# Untitled.net
KiCad netlist of a schematic drawn in EAGLE
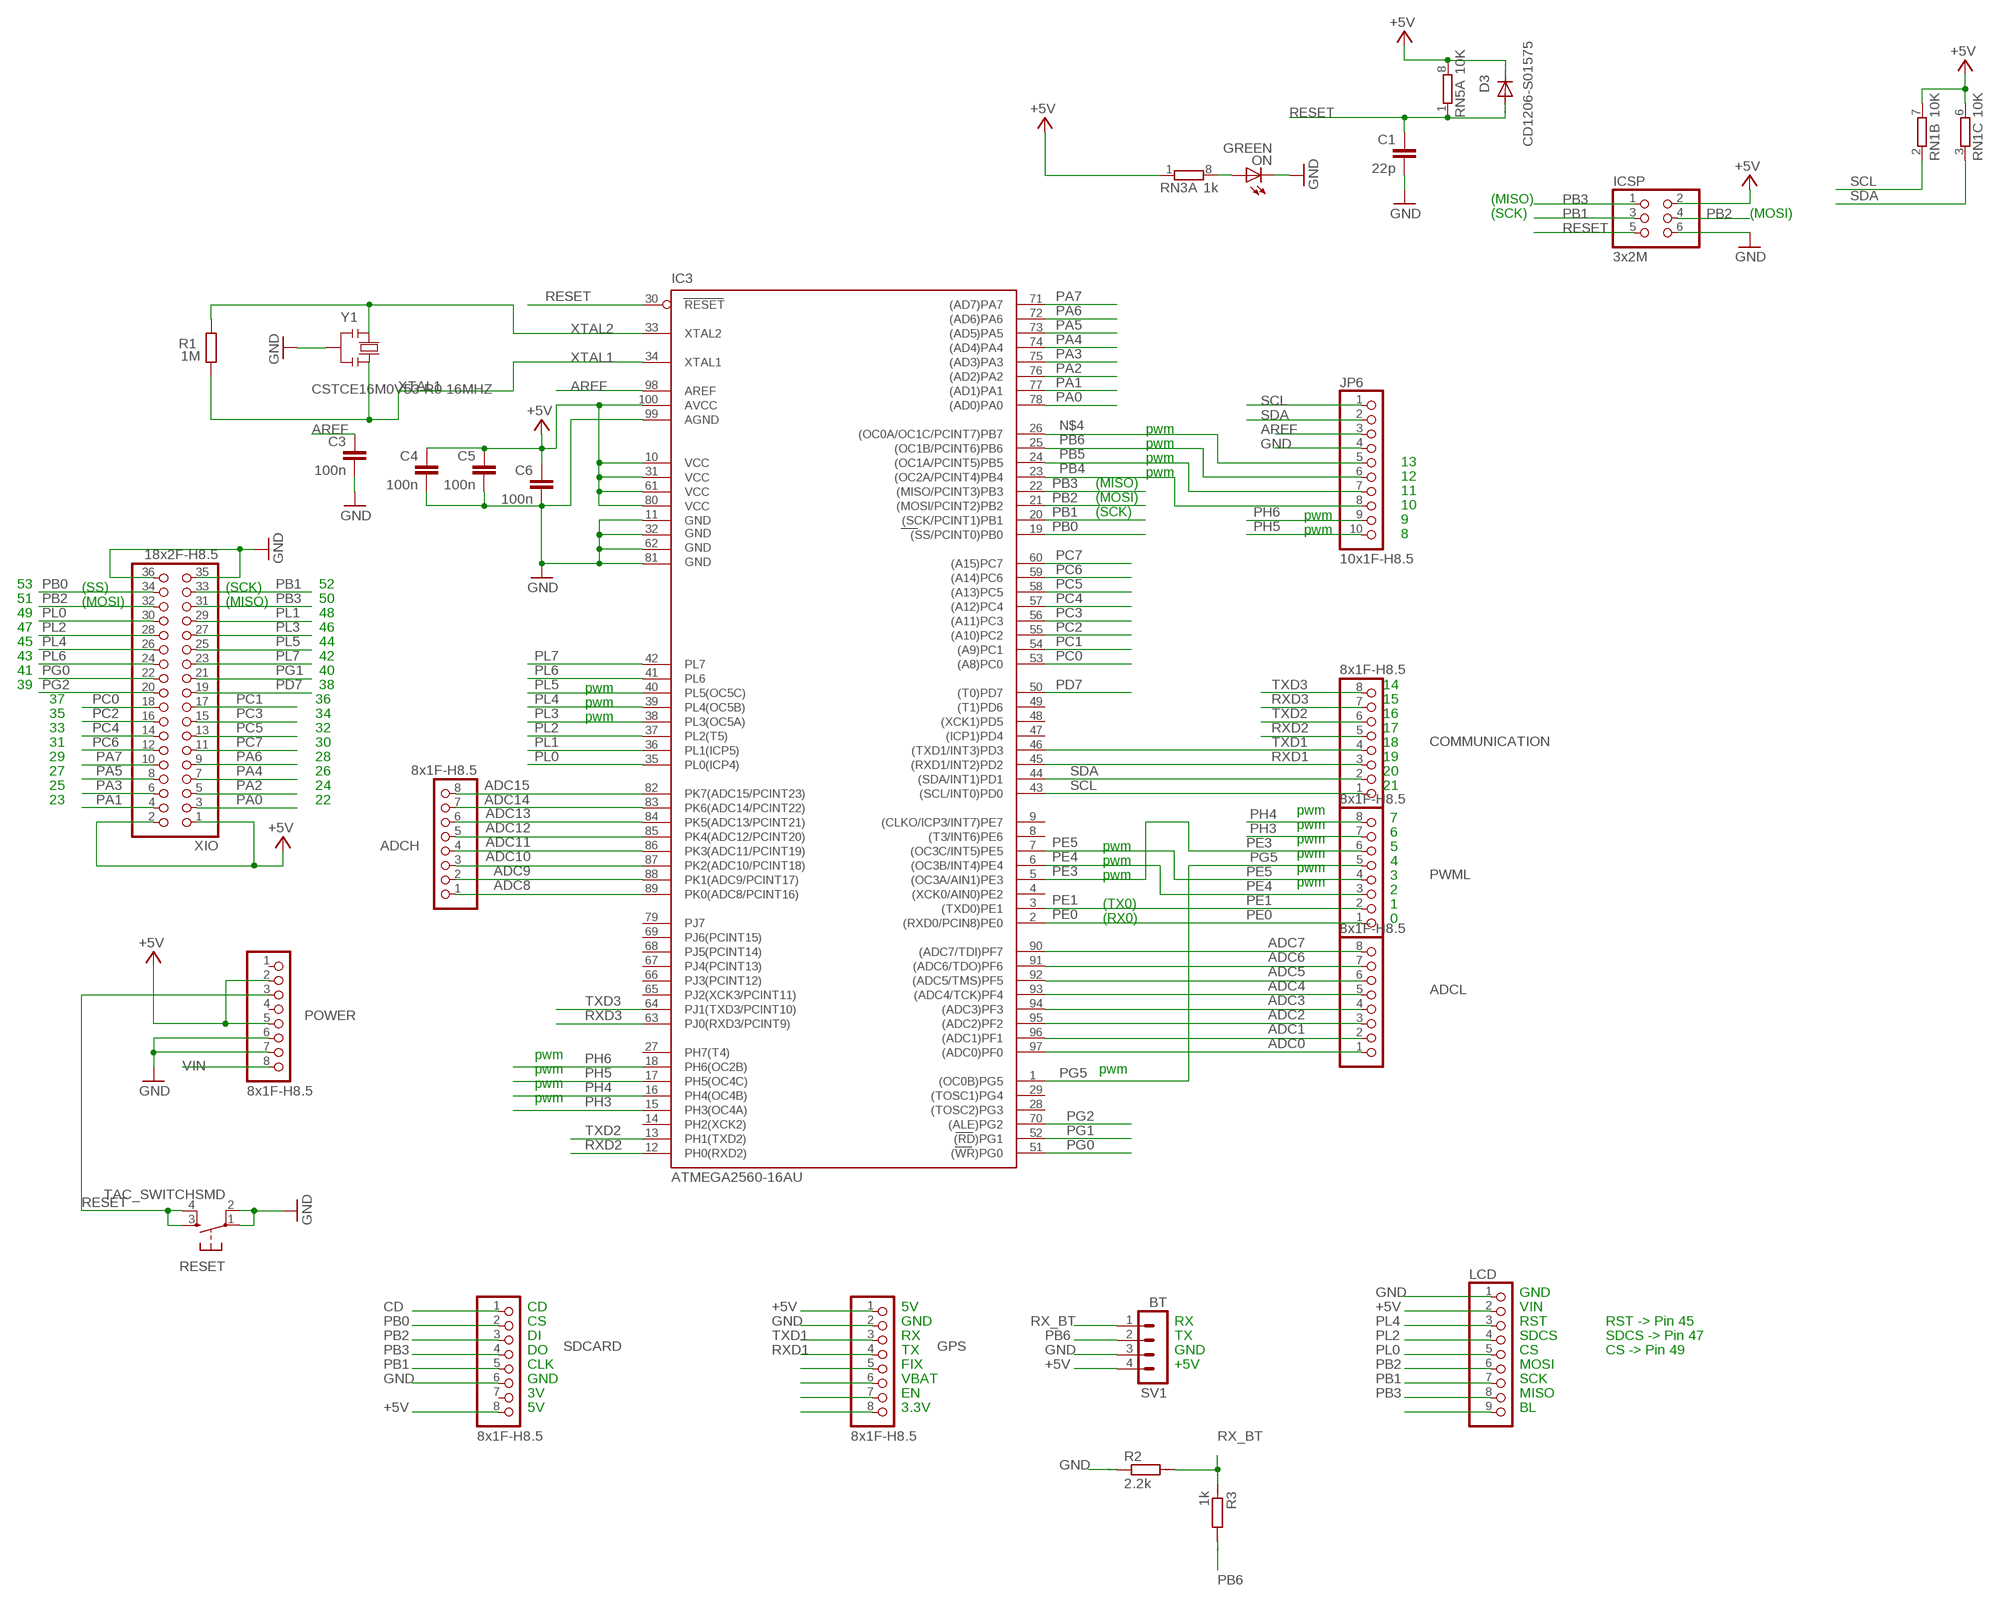
[diagram p0: schematic, sheet 1]

(export (version "E")
  (design (tool "Eeschema 10.0.6"))
  (components
    (comp (ref "ADCH")
      (value "8x1F-H8.5")
      (footprint "eagle-import:1X08")
      (libsource (lib "eagle-import") (part "PINHD-1X8"))
    )
    (comp (ref "ADCL")
      (value "8x1F-H8.5")
      (footprint "eagle-import:1X08")
      (libsource (lib "eagle-import") (part "PINHD-1X8"))
    )
    (comp (ref "C1")
      (value "22p")
      (footprint "eagle-import:C0603-ROUND")
      (libsource (lib "eagle-import") (part "C-EU0603-RND"))
    )
    (comp (ref "C3")
      (value "100n")
      (footprint "eagle-import:C0603-ROUND")
      (libsource (lib "eagle-import") (part "C-EU0603-RND"))
    )
    (comp (ref "C4")
      (value "100n")
      (footprint "eagle-import:C0603-ROUND")
      (libsource (lib "eagle-import") (part "C-EU0603-RND"))
    )
    (comp (ref "C5")
      (value "100n")
      (footprint "eagle-import:C0603-ROUND")
      (libsource (lib "eagle-import") (part "C-EU0603-RND"))
    )
    (comp (ref "C6")
      (value "100n")
      (footprint "eagle-import:C0603-ROUND")
      (libsource (lib "eagle-import") (part "C-EU0603-RND"))
    )
    (comp (ref "COMMUNICATION")
      (value "8x1F-H8.5")
      (footprint "eagle-import:1X08")
      (libsource (lib "eagle-import") (part "PINHD-1X8"))
    )
    (comp (ref "D3")
      (value "CD1206-S01575")
      (footprint "eagle-import:MINIMELF")
      (libsource (lib "eagle-import") (part "DIODE-MINIMELF"))
    )
    (comp (ref "GPS")
      (value "8x1F-H8.5")
      (footprint "eagle-import:1X08")
      (libsource (lib "eagle-import") (part "PINHD-1X8"))
    )
    (comp (ref "IC3")
      (value "ATMEGA2560-16AU")
      (footprint "eagle-import:TQFP100")
      (libsource (lib "eagle-import") (part "ATMEGA2560AU2560-16"))
    )
    (comp (ref "ICSP")
      (value "3x2M")
      (footprint "eagle-import:2X03")
      (libsource (lib "eagle-import") (part "PINHD-2X3"))
    )
    (comp (ref "JP6")
      (value "10x1F-H8.5")
      (footprint "eagle-import:1X10")
      (libsource (lib "eagle-import") (part "PINHD-1X10_ARD"))
    )
    (comp (ref "LCD")
      (value "PINHD-1X9")
      (footprint "eagle-import:1X09")
      (libsource (lib "eagle-import") (part "PINHD-1X9"))
    )
    (comp (ref "ON")
      (value "GREEN")
      (footprint "eagle-import:CHIP-LED0805")
      (libsource (lib "eagle-import") (part "LEDCHIP-LED0805"))
    )
    (comp (ref "POWER")
      (value "8x1F-H8.5")
      (footprint "eagle-import:1X08")
      (libsource (lib "eagle-import") (part "PINHD-1X8"))
    )
    (comp (ref "PWML")
      (value "8x1F-H8.5")
      (footprint "eagle-import:1X08")
      (libsource (lib "eagle-import") (part "PINHD-1X8"))
    )
    (comp (ref "R1")
      (value "1M")
      (footprint "eagle-import:R0603-ROUND")
      (libsource (lib "eagle-import") (part "R-EU_R0603"))
    )
    (comp (ref "R2")
      (value "2.2k")
      (footprint "eagle-import:R0603")
      (libsource (lib "eagle-import") (part "resistor_R-EU_R0603"))
    )
    (comp (ref "R3")
      (value "1k")
      (footprint "eagle-import:R0603")
      (libsource (lib "eagle-import") (part "resistor_R-EU_R0603"))
    )
    (comp (ref "RESET")
      (value "TAC_SWITCHSMD")
      (footprint "eagle-import:TACTILE-SWITCH-SMD")
      (libsource (lib "eagle-import") (part "TAC_SWITCHSMD"))
    )
    (comp (ref "RN1")
      (value "10K")
      (footprint "eagle-import:CAT16")
      (libsource (lib "eagle-import") (part "4R-NCAT16"))
    )
    (comp (ref "RN3")
      (value "1k")
      (footprint "eagle-import:CAY16")
      (libsource (lib "eagle-import") (part "4R-NCAY16"))
    )
    (comp (ref "RN5")
      (value "10K")
      (footprint "eagle-import:CAT16")
      (libsource (lib "eagle-import") (part "4R-NCAT16"))
    )
    (comp (ref "SDCARD")
      (value "8x1F-H8.5")
      (footprint "eagle-import:1X08")
      (libsource (lib "eagle-import") (part "PINHD-1X8"))
    )
    (comp (ref "SV1")
      (value "BT")
      (footprint "eagle-import:MA04-1")
      (libsource (lib "eagle-import") (part "MA04-1"))
    )
    (comp (ref "XIO")
      (value "18x2F-H8.5")
      (footprint "eagle-import:2X18")
      (libsource (lib "eagle-import") (part "PINHD-2X18"))
    )
    (comp (ref "Y1")
      (value "CSTCE16M0V53-R0 16MHZ")
      (footprint "eagle-import:RESONATOR")
      (libsource (lib "eagle-import") (part "RESONATORMU"))
    )
  )
  (nets
    (net (code "1") (name "+5V") (class "Default")
      (node (ref "C4") (pin "1") (pinfunction "1_1") (pintype "passive"))
      (node (ref "C5") (pin "1") (pinfunction "1_1") (pintype "passive"))
      (node (ref "C6") (pin "1") (pinfunction "1_1") (pintype "passive"))
      (node (ref "D3") (pin "C") (pinfunction "C_C") (pintype "passive"))
      (node (ref "GPS") (pin "1") (pinfunction "1_1") (pintype "passive"))
      (node (ref "IC3") (pin "10") (pinfunction "VCC_10") (pintype "power_in"))
      (node (ref "IC3") (pin "100") (pinfunction "AVCC_100") (pintype "power_in"))
      (node (ref "IC3") (pin "31") (pinfunction "VCC1_31") (pintype "power_in"))
      (node (ref "IC3") (pin "61") (pinfunction "VCC2_61") (pintype "power_in"))
      (node (ref "IC3") (pin "80") (pinfunction "VCC3_80") (pintype "power_in"))
      (node (ref "ICSP") (pin "2") (pinfunction "2_2") (pintype "passive"))
      (node (ref "LCD") (pin "2") (pinfunction "2_2") (pintype "passive"))
      (node (ref "POWER") (pin "2") (pinfunction "2_2") (pintype "passive"))
      (node (ref "POWER") (pin "5") (pinfunction "5_5") (pintype "passive"))
      (node (ref "RN1") (pin "6") (pinfunction "2_6") (pintype "passive"))
      (node (ref "RN1") (pin "7") (pinfunction "2_7") (pintype "passive"))
      (node (ref "RN3") (pin "1") (pinfunction "1_1") (pintype "passive"))
      (node (ref "RN5") (pin "8") (pinfunction "2_8") (pintype "passive"))
      (node (ref "SDCARD") (pin "8") (pinfunction "8_8") (pintype "passive"))
      (node (ref "SV1") (pin "4") (pinfunction "4_4") (pintype "passive"))
      (node (ref "XIO") (pin "1") (pinfunction "1_1") (pintype "passive"))
      (node (ref "XIO") (pin "2") (pinfunction "2_2") (pintype "passive"))
    )
    (net (code "2") (name "/ADC0") (class "Default")
      (node (ref "ADCL") (pin "1") (pinfunction "1_1") (pintype "passive"))
      (node (ref "IC3") (pin "97") (pinfunction "(ADC0)PF0_97") (pintype "bidirectional"))
    )
    (net (code "3") (name "/ADC1") (class "Default")
      (node (ref "ADCL") (pin "2") (pinfunction "2_2") (pintype "passive"))
      (node (ref "IC3") (pin "96") (pinfunction "(ADC1)PF1_96") (pintype "bidirectional"))
    )
    (net (code "4") (name "/ADC2") (class "Default")
      (node (ref "ADCL") (pin "3") (pinfunction "3_3") (pintype "passive"))
      (node (ref "IC3") (pin "95") (pinfunction "(ADC2)PF2_95") (pintype "bidirectional"))
    )
    (net (code "5") (name "/ADC3") (class "Default")
      (node (ref "ADCL") (pin "4") (pinfunction "4_4") (pintype "passive"))
      (node (ref "IC3") (pin "94") (pinfunction "(ADC3)PF3_94") (pintype "bidirectional"))
    )
    (net (code "6") (name "/ADC4") (class "Default")
      (node (ref "ADCL") (pin "5") (pinfunction "5_5") (pintype "passive"))
      (node (ref "IC3") (pin "93") (pinfunction "(ADC4/TCK)PF4_93") (pintype "bidirectional"))
    )
    (net (code "7") (name "/ADC5") (class "Default")
      (node (ref "ADCL") (pin "6") (pinfunction "6_6") (pintype "passive"))
      (node (ref "IC3") (pin "92") (pinfunction "(ADC5/TMS)PF5_92") (pintype "bidirectional"))
    )
    (net (code "8") (name "/ADC6") (class "Default")
      (node (ref "ADCL") (pin "7") (pinfunction "7_7") (pintype "passive"))
      (node (ref "IC3") (pin "91") (pinfunction "(ADC6/TDO)PF6_91") (pintype "bidirectional"))
    )
    (net (code "9") (name "/ADC7") (class "Default")
      (node (ref "ADCL") (pin "8") (pinfunction "8_8") (pintype "passive"))
      (node (ref "IC3") (pin "90") (pinfunction "(ADC7/TDI)PF7_90") (pintype "bidirectional"))
    )
    (net (code "10") (name "/ADC8") (class "Default")
      (node (ref "ADCH") (pin "1") (pinfunction "1_1") (pintype "passive"))
      (node (ref "IC3") (pin "89") (pinfunction "PK0(ADC8/PCINT16)_89") (pintype "bidirectional"))
    )
    (net (code "11") (name "/ADC9") (class "Default")
      (node (ref "ADCH") (pin "2") (pinfunction "2_2") (pintype "passive"))
      (node (ref "IC3") (pin "88") (pinfunction "PK1(ADC9/PCINT17)_88") (pintype "bidirectional"))
    )
    (net (code "12") (name "/ADC10") (class "Default")
      (node (ref "ADCH") (pin "3") (pinfunction "3_3") (pintype "passive"))
      (node (ref "IC3") (pin "87") (pinfunction "PK2(ADC10/PCINT18)_87") (pintype "bidirectional"))
    )
    (net (code "13") (name "/ADC11") (class "Default")
      (node (ref "ADCH") (pin "4") (pinfunction "4_4") (pintype "passive"))
      (node (ref "IC3") (pin "86") (pinfunction "PK3(ADC11/PCINT19)_86") (pintype "bidirectional"))
    )
    (net (code "14") (name "/ADC12") (class "Default")
      (node (ref "ADCH") (pin "5") (pinfunction "5_5") (pintype "passive"))
      (node (ref "IC3") (pin "85") (pinfunction "PK4(ADC12/PCINT20)_85") (pintype "bidirectional"))
    )
    (net (code "15") (name "/ADC13") (class "Default")
      (node (ref "ADCH") (pin "6") (pinfunction "6_6") (pintype "passive"))
      (node (ref "IC3") (pin "84") (pinfunction "PK5(ADC13/PCINT21)_84") (pintype "bidirectional"))
    )
    (net (code "16") (name "/ADC14") (class "Default")
      (node (ref "ADCH") (pin "7") (pinfunction "7_7") (pintype "passive"))
      (node (ref "IC3") (pin "83") (pinfunction "PK6(ADC14/PCINT22)_83") (pintype "bidirectional"))
    )
    (net (code "17") (name "/ADC15") (class "Default")
      (node (ref "ADCH") (pin "8") (pinfunction "8_8") (pintype "passive"))
      (node (ref "IC3") (pin "82") (pinfunction "PK7(ADC15/PCINT23)_82") (pintype "bidirectional"))
    )
    (net (code "18") (name "/AREF") (class "Default")
      (node (ref "C3") (pin "1") (pinfunction "1_1") (pintype "passive"))
      (node (ref "IC3") (pin "98") (pinfunction "AREF_98") (pintype "bidirectional"))
      (node (ref "JP6") (pin "3") (pinfunction "3_3") (pintype "passive"))
    )
    (net (code "19") (name "/CD") (class "Default")
      (node (ref "SDCARD") (pin "1") (pinfunction "1_1") (pintype "passive"))
    )
    (net (code "20") (name "/N$4") (class "Default")
      (node (ref "IC3") (pin "26") (pinfunction "(OC0A/OC1C/PCINT7)PB7_26") (pintype "bidirectional"))
      (node (ref "JP6") (pin "5") (pinfunction "5_5") (pintype "passive"))
    )
    (net (code "21") (name "/PA0") (class "Default")
      (node (ref "IC3") (pin "78") (pinfunction "(AD0)PA0_78") (pintype "bidirectional"))
      (node (ref "XIO") (pin "3") (pinfunction "3_3") (pintype "passive"))
    )
    (net (code "22") (name "/PA1") (class "Default")
      (node (ref "IC3") (pin "77") (pinfunction "(AD1)PA1_77") (pintype "bidirectional"))
      (node (ref "XIO") (pin "4") (pinfunction "4_4") (pintype "passive"))
    )
    (net (code "23") (name "/PA2") (class "Default")
      (node (ref "IC3") (pin "76") (pinfunction "(AD2)PA2_76") (pintype "bidirectional"))
      (node (ref "XIO") (pin "5") (pinfunction "5_5") (pintype "passive"))
    )
    (net (code "24") (name "/PA3") (class "Default")
      (node (ref "IC3") (pin "75") (pinfunction "(AD3)PA3_75") (pintype "bidirectional"))
      (node (ref "XIO") (pin "6") (pinfunction "6_6") (pintype "passive"))
    )
    (net (code "25") (name "/PA4") (class "Default")
      (node (ref "IC3") (pin "74") (pinfunction "(AD4)PA4_74") (pintype "bidirectional"))
      (node (ref "XIO") (pin "7") (pinfunction "7_7") (pintype "passive"))
    )
    (net (code "26") (name "/PA5") (class "Default")
      (node (ref "IC3") (pin "73") (pinfunction "(AD5)PA5_73") (pintype "bidirectional"))
      (node (ref "XIO") (pin "8") (pinfunction "8_8") (pintype "passive"))
    )
    (net (code "27") (name "/PA6") (class "Default")
      (node (ref "IC3") (pin "72") (pinfunction "(AD6)PA6_72") (pintype "bidirectional"))
      (node (ref "XIO") (pin "9") (pinfunction "9_9") (pintype "passive"))
    )
    (net (code "28") (name "/PA7") (class "Default")
      (node (ref "IC3") (pin "71") (pinfunction "(AD7)PA7_71") (pintype "bidirectional"))
      (node (ref "XIO") (pin "10") (pinfunction "10_10") (pintype "passive"))
    )
    (net (code "29") (name "/PB0") (class "Default")
      (node (ref "IC3") (pin "19") (pinfunction "(SS/PCINT0)PB0_19") (pintype "bidirectional"))
      (node (ref "SDCARD") (pin "2") (pinfunction "2_2") (pintype "passive"))
      (node (ref "XIO") (pin "34") (pinfunction "34_34") (pintype "passive"))
    )
    (net (code "30") (name "/PB1") (class "Default")
      (node (ref "IC3") (pin "20") (pinfunction "(SCK/PCINT1)PB1_20") (pintype "bidirectional"))
      (node (ref "ICSP") (pin "3") (pinfunction "3_3") (pintype "passive"))
      (node (ref "LCD") (pin "7") (pinfunction "7_7") (pintype "passive"))
      (node (ref "SDCARD") (pin "5") (pinfunction "5_5") (pintype "passive"))
      (node (ref "XIO") (pin "33") (pinfunction "33_33") (pintype "passive"))
    )
    (net (code "31") (name "/PB2") (class "Default")
      (node (ref "IC3") (pin "21") (pinfunction "(MOSI/PCINT2)PB2_21") (pintype "bidirectional"))
      (node (ref "ICSP") (pin "4") (pinfunction "4_4") (pintype "passive"))
      (node (ref "LCD") (pin "6") (pinfunction "6_6") (pintype "passive"))
      (node (ref "SDCARD") (pin "3") (pinfunction "3_3") (pintype "passive"))
      (node (ref "XIO") (pin "32") (pinfunction "32_32") (pintype "passive"))
    )
    (net (code "32") (name "/PB3") (class "Default")
      (node (ref "IC3") (pin "22") (pinfunction "(MISO/PCINT3)PB3_22") (pintype "bidirectional"))
      (node (ref "ICSP") (pin "1") (pinfunction "1_1") (pintype "passive"))
      (node (ref "LCD") (pin "8") (pinfunction "8_8") (pintype "passive"))
      (node (ref "SDCARD") (pin "4") (pinfunction "4_4") (pintype "passive"))
      (node (ref "XIO") (pin "31") (pinfunction "31_31") (pintype "passive"))
    )
    (net (code "33") (name "/PB4") (class "Default")
      (node (ref "IC3") (pin "23") (pinfunction "(OC2A/PCINT4)PB4_23") (pintype "bidirectional"))
      (node (ref "JP6") (pin "8") (pinfunction "8_8") (pintype "passive"))
    )
    (net (code "34") (name "/PB5") (class "Default")
      (node (ref "IC3") (pin "24") (pinfunction "(OC1A/PCINT5)PB5_24") (pintype "bidirectional"))
      (node (ref "JP6") (pin "7") (pinfunction "7_7") (pintype "passive"))
    )
    (net (code "35") (name "/PB6") (class "Default")
      (node (ref "IC3") (pin "25") (pinfunction "(OC1B/PCINT6)PB6_25") (pintype "bidirectional"))
      (node (ref "JP6") (pin "6") (pinfunction "6_6") (pintype "passive"))
      (node (ref "R3") (pin "2") (pinfunction "2_2") (pintype "passive"))
      (node (ref "SV1") (pin "2") (pinfunction "2_2") (pintype "passive"))
    )
    (net (code "36") (name "/PC0") (class "Default")
      (node (ref "IC3") (pin "53") (pinfunction "(A8)PC0_53") (pintype "bidirectional"))
      (node (ref "XIO") (pin "18") (pinfunction "18_18") (pintype "passive"))
    )
    (net (code "37") (name "/PC1") (class "Default")
      (node (ref "IC3") (pin "54") (pinfunction "(A9)PC1_54") (pintype "bidirectional"))
      (node (ref "XIO") (pin "17") (pinfunction "17_17") (pintype "passive"))
    )
    (net (code "38") (name "/PC2") (class "Default")
      (node (ref "IC3") (pin "55") (pinfunction "(A10)PC2_55") (pintype "bidirectional"))
      (node (ref "XIO") (pin "16") (pinfunction "16_16") (pintype "passive"))
    )
    (net (code "39") (name "/PC3") (class "Default")
      (node (ref "IC3") (pin "56") (pinfunction "(A11)PC3_56") (pintype "bidirectional"))
      (node (ref "XIO") (pin "15") (pinfunction "15_15") (pintype "passive"))
    )
    (net (code "40") (name "/PC4") (class "Default")
      (node (ref "IC3") (pin "57") (pinfunction "(A12)PC4_57") (pintype "bidirectional"))
      (node (ref "XIO") (pin "14") (pinfunction "14_14") (pintype "passive"))
    )
    (net (code "41") (name "/PC5") (class "Default")
      (node (ref "IC3") (pin "58") (pinfunction "(A13)PC5_58") (pintype "bidirectional"))
      (node (ref "XIO") (pin "13") (pinfunction "13_13") (pintype "passive"))
    )
    (net (code "42") (name "/PC6") (class "Default")
      (node (ref "IC3") (pin "59") (pinfunction "(A14)PC6_59") (pintype "bidirectional"))
      (node (ref "XIO") (pin "12") (pinfunction "12_12") (pintype "passive"))
    )
    (net (code "43") (name "/PC7") (class "Default")
      (node (ref "IC3") (pin "60") (pinfunction "(A15)PC7_60") (pintype "bidirectional"))
      (node (ref "XIO") (pin "11") (pinfunction "11_11") (pintype "passive"))
    )
    (net (code "44") (name "/PD7") (class "Default")
      (node (ref "IC3") (pin "50") (pinfunction "(T0)PD7_50") (pintype "bidirectional"))
      (node (ref "XIO") (pin "19") (pinfunction "19_19") (pintype "passive"))
    )
    (net (code "45") (name "/PE0") (class "Default")
      (node (ref "IC3") (pin "2") (pinfunction "(RXD0/PCIN8)PE0_2") (pintype "bidirectional"))
      (node (ref "PWML") (pin "1") (pinfunction "1_1") (pintype "passive"))
    )
    (net (code "46") (name "/PE1") (class "Default")
      (node (ref "IC3") (pin "3") (pinfunction "(TXD0)PE1_3") (pintype "bidirectional"))
      (node (ref "PWML") (pin "2") (pinfunction "2_2") (pintype "passive"))
    )
    (net (code "47") (name "/PE3") (class "Default")
      (node (ref "IC3") (pin "5") (pinfunction "(OC3A/AIN1)PE3_5") (pintype "bidirectional"))
      (node (ref "PWML") (pin "6") (pinfunction "6_6") (pintype "passive"))
    )
    (net (code "48") (name "/PE4") (class "Default")
      (node (ref "IC3") (pin "6") (pinfunction "(OC3B/INT4)PE4_6") (pintype "bidirectional"))
      (node (ref "PWML") (pin "3") (pinfunction "3_3") (pintype "passive"))
    )
    (net (code "49") (name "/PE5") (class "Default")
      (node (ref "IC3") (pin "7") (pinfunction "(OC3C/INT5)PE5_7") (pintype "bidirectional"))
      (node (ref "PWML") (pin "4") (pinfunction "4_4") (pintype "passive"))
    )
    (net (code "50") (name "/PG0") (class "Default")
      (node (ref "IC3") (pin "51") (pinfunction "(WR)PG0_51") (pintype "bidirectional"))
      (node (ref "XIO") (pin "22") (pinfunction "22_22") (pintype "passive"))
    )
    (net (code "51") (name "/PG1") (class "Default")
      (node (ref "IC3") (pin "52") (pinfunction "(RD)PG1_52") (pintype "bidirectional"))
      (node (ref "XIO") (pin "21") (pinfunction "21_21") (pintype "passive"))
    )
    (net (code "52") (name "/PG2") (class "Default")
      (node (ref "IC3") (pin "70") (pinfunction "(ALE)PG2_70") (pintype "bidirectional"))
      (node (ref "XIO") (pin "20") (pinfunction "20_20") (pintype "passive"))
    )
    (net (code "53") (name "/PG5") (class "Default")
      (node (ref "IC3") (pin "1") (pinfunction "(OC0B)PG5_1") (pintype "bidirectional"))
      (node (ref "PWML") (pin "5") (pinfunction "5_5") (pintype "passive"))
    )
    (net (code "54") (name "/PH3") (class "Default")
      (node (ref "IC3") (pin "15") (pinfunction "PH3(OC4A)_15") (pintype "bidirectional"))
      (node (ref "PWML") (pin "7") (pinfunction "7_7") (pintype "passive"))
    )
    (net (code "55") (name "/PH4") (class "Default")
      (node (ref "IC3") (pin "16") (pinfunction "PH4(OC4B)_16") (pintype "bidirectional"))
      (node (ref "PWML") (pin "8") (pinfunction "8_8") (pintype "passive"))
    )
    (net (code "56") (name "/PH5") (class "Default")
      (node (ref "IC3") (pin "17") (pinfunction "PH5(OC4C)_17") (pintype "bidirectional"))
      (node (ref "JP6") (pin "10") (pinfunction "10_10") (pintype "passive"))
    )
    (net (code "57") (name "/PH6") (class "Default")
      (node (ref "IC3") (pin "18") (pinfunction "PH6(OC2B)_18") (pintype "bidirectional"))
      (node (ref "JP6") (pin "9") (pinfunction "9_9") (pintype "passive"))
    )
    (net (code "58") (name "/PL0") (class "Default")
      (node (ref "IC3") (pin "35") (pinfunction "PL0(ICP4)_35") (pintype "bidirectional"))
      (node (ref "LCD") (pin "5") (pinfunction "5_5") (pintype "passive"))
      (node (ref "XIO") (pin "30") (pinfunction "30_30") (pintype "passive"))
    )
    (net (code "59") (name "/PL1") (class "Default")
      (node (ref "IC3") (pin "36") (pinfunction "PL1(ICP5)_36") (pintype "bidirectional"))
      (node (ref "XIO") (pin "29") (pinfunction "29_29") (pintype "passive"))
    )
    (net (code "60") (name "/PL2") (class "Default")
      (node (ref "IC3") (pin "37") (pinfunction "PL2(T5)_37") (pintype "bidirectional"))
      (node (ref "LCD") (pin "4") (pinfunction "4_4") (pintype "passive"))
      (node (ref "XIO") (pin "28") (pinfunction "28_28") (pintype "passive"))
    )
    (net (code "61") (name "/PL3") (class "Default")
      (node (ref "IC3") (pin "38") (pinfunction "PL3(OC5A)_38") (pintype "bidirectional"))
      (node (ref "XIO") (pin "27") (pinfunction "27_27") (pintype "passive"))
    )
    (net (code "62") (name "/PL4") (class "Default")
      (node (ref "IC3") (pin "39") (pinfunction "PL4(OC5B)_39") (pintype "bidirectional"))
      (node (ref "LCD") (pin "3") (pinfunction "3_3") (pintype "passive"))
      (node (ref "XIO") (pin "26") (pinfunction "26_26") (pintype "passive"))
    )
    (net (code "63") (name "/PL5") (class "Default")
      (node (ref "IC3") (pin "40") (pinfunction "PL5(OC5C)_40") (pintype "bidirectional"))
      (node (ref "XIO") (pin "25") (pinfunction "25_25") (pintype "passive"))
    )
    (net (code "64") (name "/PL6") (class "Default")
      (node (ref "IC3") (pin "41") (pinfunction "PL6_41") (pintype "bidirectional"))
      (node (ref "XIO") (pin "24") (pinfunction "24_24") (pintype "passive"))
    )
    (net (code "65") (name "/PL7") (class "Default")
      (node (ref "IC3") (pin "42") (pinfunction "PL7_42") (pintype "bidirectional"))
      (node (ref "XIO") (pin "23") (pinfunction "23_23") (pintype "passive"))
    )
    (net (code "66") (name "/RESET") (class "Default")
      (node (ref "C1") (pin "1") (pinfunction "1_1") (pintype "passive"))
      (node (ref "D3") (pin "A") (pinfunction "A_A") (pintype "passive"))
      (node (ref "IC3") (pin "30") (pinfunction "RESET_30") (pintype "input"))
      (node (ref "ICSP") (pin "5") (pinfunction "5_5") (pintype "passive"))
      (node (ref "POWER") (pin "3") (pinfunction "3_3") (pintype "passive"))
      (node (ref "RESET") (pin "3") (pinfunction "3_3") (pintype "passive"))
      (node (ref "RESET") (pin "4") (pinfunction "4_4") (pintype "passive"))
      (node (ref "RN5") (pin "1") (pinfunction "1_1") (pintype "passive"))
    )
    (net (code "67") (name "/RXD1") (class "Default")
      (node (ref "COMMUNICATION") (pin "3") (pinfunction "3_3") (pintype "passive"))
      (node (ref "GPS") (pin "4") (pinfunction "4_4") (pintype "passive"))
      (node (ref "IC3") (pin "45") (pinfunction "(RXD1/INT2)PD2_45") (pintype "bidirectional"))
    )
    (net (code "68") (name "/RXD2") (class "Default")
      (node (ref "COMMUNICATION") (pin "5") (pinfunction "5_5") (pintype "passive"))
      (node (ref "IC3") (pin "12") (pinfunction "PH0(RXD2)_12") (pintype "bidirectional"))
    )
    (net (code "69") (name "/RXD3") (class "Default")
      (node (ref "COMMUNICATION") (pin "7") (pinfunction "7_7") (pintype "passive"))
      (node (ref "IC3") (pin "63") (pinfunction "PJ0(RXD3/PCINT9)_63") (pintype "bidirectional"))
    )
    (net (code "70") (name "/RX_BT") (class "Default")
      (node (ref "R2") (pin "2") (pinfunction "2_2") (pintype "passive"))
      (node (ref "R3") (pin "1") (pinfunction "1_1") (pintype "passive"))
      (node (ref "SV1") (pin "1") (pinfunction "1_1") (pintype "passive"))
    )
    (net (code "71") (name "/SCL") (class "Default")
      (node (ref "COMMUNICATION") (pin "1") (pinfunction "1_1") (pintype "passive"))
      (node (ref "IC3") (pin "43") (pinfunction "(SCL/INT0)PD0_43") (pintype "bidirectional"))
      (node (ref "JP6") (pin "1") (pinfunction "1_1") (pintype "passive"))
      (node (ref "RN1") (pin "2") (pinfunction "1_2") (pintype "passive"))
    )
    (net (code "72") (name "/SDA") (class "Default")
      (node (ref "COMMUNICATION") (pin "2") (pinfunction "2_2") (pintype "passive"))
      (node (ref "IC3") (pin "44") (pinfunction "(SDA/INT1)PD1_44") (pintype "bidirectional"))
      (node (ref "JP6") (pin "2") (pinfunction "2_2") (pintype "passive"))
      (node (ref "RN1") (pin "3") (pinfunction "1_3") (pintype "passive"))
    )
    (net (code "73") (name "/TXD1") (class "Default")
      (node (ref "COMMUNICATION") (pin "4") (pinfunction "4_4") (pintype "passive"))
      (node (ref "GPS") (pin "3") (pinfunction "3_3") (pintype "passive"))
      (node (ref "IC3") (pin "46") (pinfunction "(TXD1/INT3)PD3_46") (pintype "bidirectional"))
    )
    (net (code "74") (name "/TXD2") (class "Default")
      (node (ref "COMMUNICATION") (pin "6") (pinfunction "6_6") (pintype "passive"))
      (node (ref "IC3") (pin "13") (pinfunction "PH1(TXD2)_13") (pintype "bidirectional"))
    )
    (net (code "75") (name "/TXD3") (class "Default")
      (node (ref "COMMUNICATION") (pin "8") (pinfunction "8_8") (pintype "passive"))
      (node (ref "IC3") (pin "64") (pinfunction "PJ1(TXD3/PCINT10)_64") (pintype "bidirectional"))
    )
    (net (code "76") (name "/VIN") (class "Default")
      (node (ref "POWER") (pin "8") (pinfunction "8_8") (pintype "passive"))
    )
    (net (code "77") (name "/XTAL1") (class "Default")
      (node (ref "IC3") (pin "34") (pinfunction "XTAL1_34") (pintype "input"))
      (node (ref "R1") (pin "1") (pinfunction "1_1") (pintype "passive"))
      (node (ref "Y1") (pin "3") (pinfunction "3_3") (pintype "passive"))
    )
    (net (code "78") (name "/XTAL2") (class "Default")
      (node (ref "IC3") (pin "33") (pinfunction "XTAL2_33") (pintype "output"))
      (node (ref "R1") (pin "2") (pinfunction "2_2") (pintype "passive"))
      (node (ref "Y1") (pin "1") (pinfunction "1_1") (pintype "passive"))
    )
    (net (code "79") (name "GND") (class "Default")
      (node (ref "C1") (pin "2") (pinfunction "2_2") (pintype "passive"))
      (node (ref "C3") (pin "2") (pinfunction "2_2") (pintype "passive"))
      (node (ref "C4") (pin "2") (pinfunction "2_2") (pintype "passive"))
      (node (ref "C5") (pin "2") (pinfunction "2_2") (pintype "passive"))
      (node (ref "C6") (pin "2") (pinfunction "2_2") (pintype "passive"))
      (node (ref "GPS") (pin "2") (pinfunction "2_2") (pintype "passive"))
      (node (ref "IC3") (pin "11") (pinfunction "GND_11") (pintype "power_in"))
      (node (ref "IC3") (pin "32") (pinfunction "GND1_32") (pintype "power_in"))
      (node (ref "IC3") (pin "62") (pinfunction "GND2_62") (pintype "power_in"))
      (node (ref "IC3") (pin "81") (pinfunction "GND3_81") (pintype "power_in"))
      (node (ref "IC3") (pin "99") (pinfunction "AGND_99") (pintype "power_in"))
      (node (ref "ICSP") (pin "6") (pinfunction "6_6") (pintype "passive"))
      (node (ref "JP6") (pin "4") (pinfunction "4_4") (pintype "passive"))
      (node (ref "LCD") (pin "1") (pinfunction "1_1") (pintype "passive"))
      (node (ref "ON") (pin "C") (pinfunction "C_C") (pintype "passive"))
      (node (ref "POWER") (pin "6") (pinfunction "6_6") (pintype "passive"))
      (node (ref "POWER") (pin "7") (pinfunction "7_7") (pintype "passive"))
      (node (ref "R2") (pin "1") (pinfunction "1_1") (pintype "passive"))
      (node (ref "RESET") (pin "1") (pinfunction "1_1") (pintype "passive"))
      (node (ref "RESET") (pin "2") (pinfunction "2_2") (pintype "passive"))
      (node (ref "SDCARD") (pin "6") (pinfunction "6_6") (pintype "passive"))
      (node (ref "SV1") (pin "3") (pinfunction "3_3") (pintype "passive"))
      (node (ref "XIO") (pin "35") (pinfunction "35_35") (pintype "passive"))
      (node (ref "XIO") (pin "36") (pinfunction "36_36") (pintype "passive"))
      (node (ref "Y1") (pin "2") (pinfunction "2_2") (pintype "passive"))
    )
    (net (code "80") (name "Net-(RN3A-2)") (class "Default")
      (node (ref "ON") (pin "A") (pinfunction "A_A") (pintype "passive"))
      (node (ref "RN3") (pin "8") (pinfunction "2_8") (pintype "passive"))
    )
    (net (code "81") (name "unconnected-(GPS-Pad5)") (class "Default")
      (node (ref "GPS") (pin "5") (pinfunction "5_5") (pintype "passive"))
    )
    (net (code "82") (name "unconnected-(GPS-Pad6)") (class "Default")
      (node (ref "GPS") (pin "6") (pinfunction "6_6") (pintype "passive"))
    )
    (net (code "83") (name "unconnected-(GPS-Pad7)") (class "Default")
      (node (ref "GPS") (pin "7") (pinfunction "7_7") (pintype "passive"))
    )
    (net (code "84") (name "unconnected-(GPS-Pad8)") (class "Default")
      (node (ref "GPS") (pin "8") (pinfunction "8_8") (pintype "passive"))
    )
    (net (code "85") (name "unconnected-(IC3-(CLKO{slash}ICP3{slash}INT7)PE7-Pad9)") (class "Default")
      (node (ref "IC3") (pin "9") (pinfunction "(CLKO/ICP3/INT7)PE7_9") (pintype "bidirectional"))
    )
    (net (code "86") (name "unconnected-(IC3-(ICP1)PD4-Pad47)") (class "Default")
      (node (ref "IC3") (pin "47") (pinfunction "(ICP1)PD4_47") (pintype "bidirectional"))
    )
    (net (code "87") (name "unconnected-(IC3-(T1)PD6-Pad49)") (class "Default")
      (node (ref "IC3") (pin "49") (pinfunction "(T1)PD6_49") (pintype "bidirectional"))
    )
    (net (code "88") (name "unconnected-(IC3-(T3{slash}INT6)PE6-Pad8)") (class "Default")
      (node (ref "IC3") (pin "8") (pinfunction "(T3/INT6)PE6_8") (pintype "bidirectional"))
    )
    (net (code "89") (name "unconnected-(IC3-(TOSC1)PG4-Pad29)") (class "Default")
      (node (ref "IC3") (pin "29") (pinfunction "(TOSC1)PG4_29") (pintype "bidirectional"))
    )
    (net (code "90") (name "unconnected-(IC3-(TOSC2)PG3-Pad28)") (class "Default")
      (node (ref "IC3") (pin "28") (pinfunction "(TOSC2)PG3_28") (pintype "bidirectional"))
    )
    (net (code "91") (name "unconnected-(IC3-(XCK0{slash}AIN0)PE2-Pad4)") (class "Default")
      (node (ref "IC3") (pin "4") (pinfunction "(XCK0/AIN0)PE2_4") (pintype "bidirectional"))
    )
    (net (code "92") (name "unconnected-(IC3-(XCK1)PD5-Pad48)") (class "Default")
      (node (ref "IC3") (pin "48") (pinfunction "(XCK1)PD5_48") (pintype "bidirectional"))
    )
    (net (code "93") (name "unconnected-(IC3-PH2(XCK2)-Pad14)") (class "Default")
      (node (ref "IC3") (pin "14") (pinfunction "PH2(XCK2)_14") (pintype "bidirectional"))
    )
    (net (code "94") (name "unconnected-(IC3-PH7(T4)-Pad27)") (class "Default")
      (node (ref "IC3") (pin "27") (pinfunction "PH7(T4)_27") (pintype "bidirectional"))
    )
    (net (code "95") (name "unconnected-(IC3-PJ2(XCK3{slash}PCINT11)-Pad65)") (class "Default")
      (node (ref "IC3") (pin "65") (pinfunction "PJ2(XCK3/PCINT11)_65") (pintype "bidirectional"))
    )
    (net (code "96") (name "unconnected-(IC3-PJ3(PCINT12)-Pad66)") (class "Default")
      (node (ref "IC3") (pin "66") (pinfunction "PJ3(PCINT12)_66") (pintype "bidirectional"))
    )
    (net (code "97") (name "unconnected-(IC3-PJ4(PCINT13)-Pad67)") (class "Default")
      (node (ref "IC3") (pin "67") (pinfunction "PJ4(PCINT13)_67") (pintype "bidirectional"))
    )
    (net (code "98") (name "unconnected-(IC3-PJ5(PCINT14)-Pad68)") (class "Default")
      (node (ref "IC3") (pin "68") (pinfunction "PJ5(PCINT14)_68") (pintype "bidirectional"))
    )
    (net (code "99") (name "unconnected-(IC3-PJ6(PCINT15)-Pad69)") (class "Default")
      (node (ref "IC3") (pin "69") (pinfunction "PJ6(PCINT15)_69") (pintype "bidirectional"))
    )
    (net (code "100") (name "unconnected-(IC3-PJ7-Pad79)") (class "Default")
      (node (ref "IC3") (pin "79") (pinfunction "PJ7_79") (pintype "bidirectional"))
    )
    (net (code "101") (name "unconnected-(LCD-Pad9)") (class "Default")
      (node (ref "LCD") (pin "9") (pinfunction "9_9") (pintype "passive"))
    )
    (net (code "102") (name "unconnected-(POWER-Pad1)") (class "Default")
      (node (ref "POWER") (pin "1") (pinfunction "1_1") (pintype "passive"))
    )
    (net (code "103") (name "unconnected-(POWER-Pad4)") (class "Default")
      (node (ref "POWER") (pin "4") (pinfunction "4_4") (pintype "passive"))
    )
    (net (code "104") (name "unconnected-(SDCARD-Pad7)") (class "Default")
      (node (ref "SDCARD") (pin "7") (pinfunction "7_7") (pintype "passive"))
    )
  )
)
